# PG06_Schematic_Sheet4.net
KiCad netlist of a schematic drawn in Altium Designer
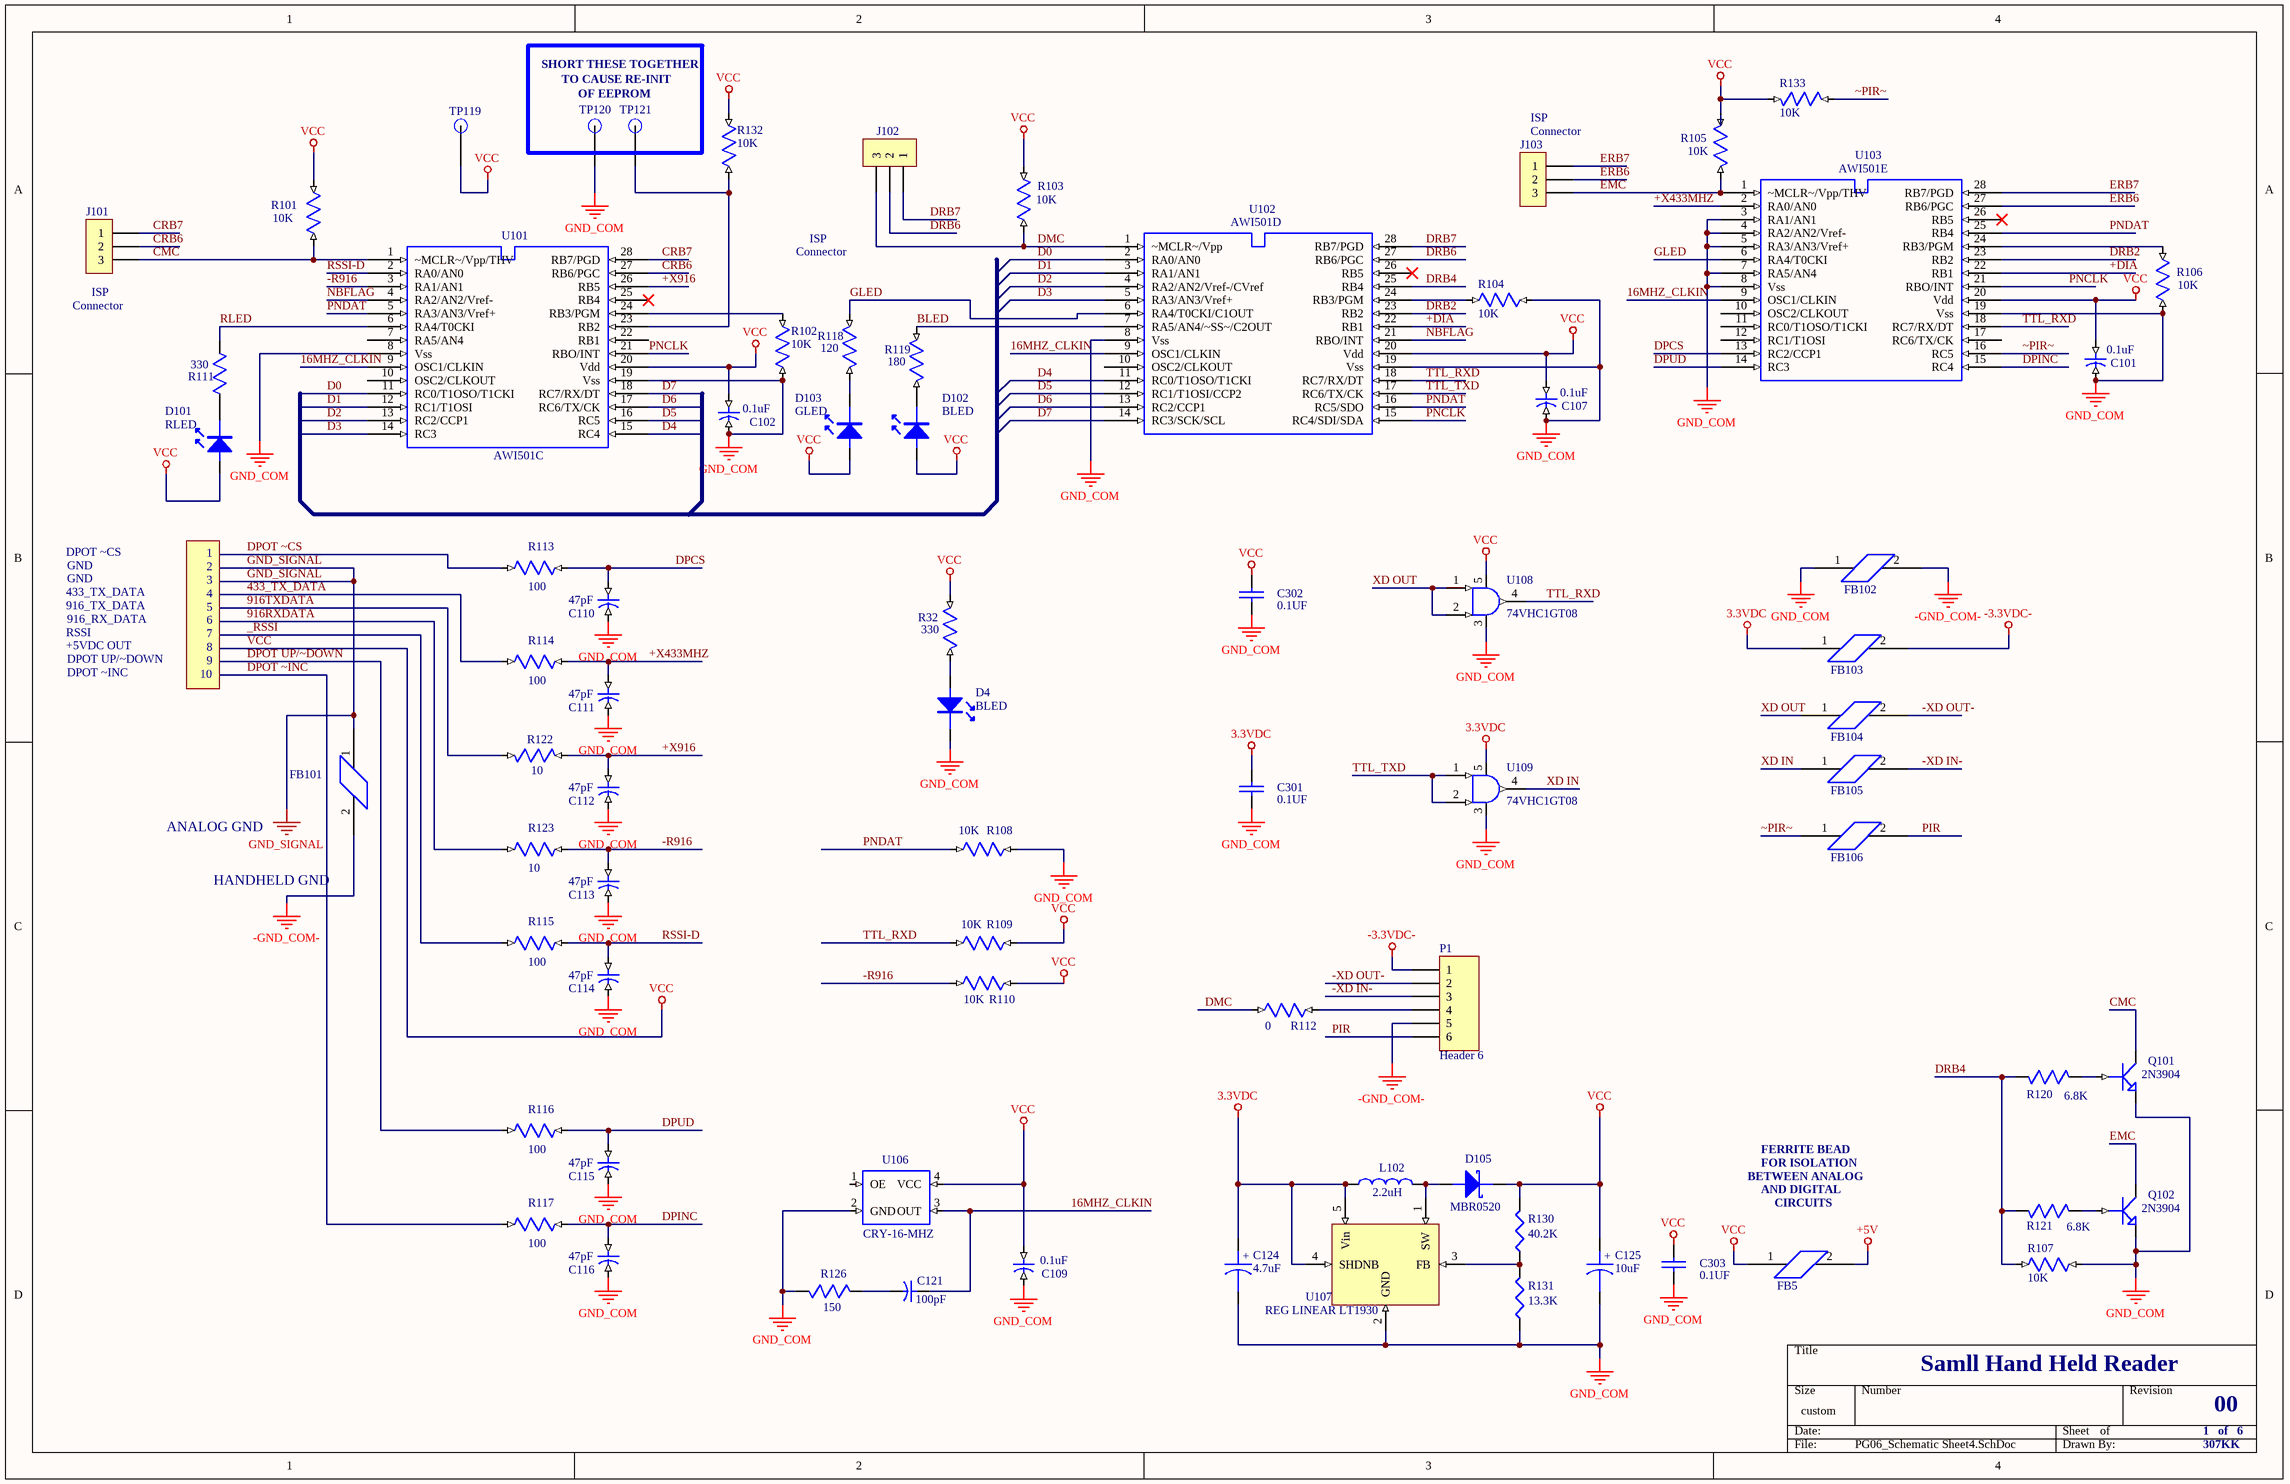
[diagram p0: PG06_Schematic Sheet4.SchDoc]

(export (version "E")
  (design (tool "Eeschema 10.0.6"))
  (components
    (comp (ref "C101") (value "0.1uF") (footprint "0603") (libsource (lib "*") (part "C_603")))
    (comp (ref "C102") (value "0.1uF") (footprint "0603") (libsource (lib "*") (part "C_603")))
    (comp (ref "C107") (value "0.1uF") (footprint "0603") (libsource (lib "*") (part "C_603")))
    (comp (ref "C109") (value "0.1uF") (footprint "0603") (libsource (lib "") (part "C_603_1")))
    (comp (ref "C110") (value "47pF") (footprint "0603") (libsource (lib "*") (part "C0603")))
    (comp (ref "C111") (value "47pF") (footprint "0603") (libsource (lib "*") (part "C0603")))
    (comp (ref "C112") (value "47pF") (footprint "0603") (libsource (lib "*") (part "C0603")))
    (comp (ref "C113") (value "47pF") (footprint "0603") (libsource (lib "*") (part "C0603")))
    (comp (ref "C114") (value "47pF") (footprint "0603") (libsource (lib "*") (part "C0603")))
    (comp (ref "C115") (value "47pF") (footprint "0603") (libsource (lib "*") (part "C0603")))
    (comp (ref "C116") (value "47pF") (footprint "0603") (libsource (lib "*") (part "C0603")))
    (comp (ref "C121") (value "100pF") (footprint "0603") (libsource (lib "*") (part "C_0603")))
    (comp (ref "C124")
      (value "4.7uF")
      (footprint "CAP A CASE")
      (description "Capacitor")
      (libsource (lib "*") (part "CAPACITOR POL"))
    )
    (comp (ref "C125")
      (value "10uF")
      (footprint "CAP A CASE")
      (description "Capacitor")
      (libsource (lib "*") (part "CAPACITOR POL"))
    )
    (comp (ref "C301")
      (value "0.1UF")
      (footprint "0603")
      (description "Capacitor")
      (libsource (lib "*") (part "CAP"))
    )
    (comp (ref "C302")
      (value "0.1UF")
      (footprint "0603")
      (description "Capacitor")
      (libsource (lib "*") (part "CAP"))
    )
    (comp (ref "C303")
      (value "0.1UF")
      (footprint "0603")
      (description "Capacitor")
      (libsource (lib "*") (part "CAP"))
    )
    (comp (ref "D4") (value "BLED") (footprint "404-1032-2-ND") (libsource (lib "*") (part "LED")))
    (comp (ref "D101") (value "RLED") (footprint "404-1032-2-ND") (libsource (lib "*") (part "LED")))
    (comp (ref "D102") (value "BLED") (footprint "404-1032-2-ND") (libsource (lib "*") (part "LED")))
    (comp (ref "D103") (value "GLED") (footprint "404-1032-2-ND") (libsource (lib "*") (part "LED")))
    (comp (ref "D105")
      (value "MBR0520")
      (footprint "SOD123_021405")
      (description "Schottky Diode")
      (libsource (lib "*") (part "DIODE SCHOTTKY"))
    )
    (comp (ref "FB5") (value "FB") (footprint "0603") (libsource (lib "*") (part "FB_0603")))
    (comp (ref "FB101") (value "FB") (footprint "0603") (libsource (lib "*") (part "FB_0603")))
    (comp (ref "FB102") (value "FB") (footprint "0603") (libsource (lib "*") (part "FB_0603")))
    (comp (ref "FB103") (value "FB") (footprint "0603") (libsource (lib "*") (part "FB_0603")))
    (comp (ref "FB104") (value "FB") (footprint "0603") (libsource (lib "*") (part "FB_0603")))
    (comp (ref "FB105") (value "FB") (footprint "0603") (libsource (lib "*") (part "FB_0603")))
    (comp (ref "FB106") (value "FB") (footprint "0603") (libsource (lib "*") (part "FB_0603")))
    (comp (ref "J101")
      (value "1X3 HEADER")
      (footprint "1X3 HEADER TEST PADS")
      (description "Connector")
      (libsource (lib "*") (part "CON3"))
    )
    (comp (ref "J102")
      (value "1X3 HEADER")
      (footprint "1X3 HEADER TEST PADS")
      (description "Connector")
      (libsource (lib "") (part "CON3_1"))
    )
    (comp (ref "J103")
      (value "1X3 HEADER")
      (footprint "1X3 HEADER TEST PADS")
      (description "Connector")
      (libsource (lib "*") (part "CON3"))
    )
    (comp (ref "L102")
      (value "2.2uH")
      (footprint "COIL BOURNS SDR7030-330M")
      (libsource (lib "*") (part "INDUCTOR1"))
    )
    (comp (ref "P1")
      (value "Header 6")
      (footprint "1X6 HEADER")
      (description "Header, 6-Pin")
      (fields (field (name "PUBLISHER") "Altium Limited"))
      (libsource (lib "Miscellaneous Connectors") (part "Header 6"))
    )
    (comp (ref "Q101")
      (value "2N3904")
      (footprint "SOT23 TRANS")
      (description "NPN Transistor")
      (libsource (lib "*") (part "NPN1"))
    )
    (comp (ref "Q102")
      (value "2N3904")
      (footprint "SOT23 TRANS")
      (description "NPN Transistor")
      (libsource (lib "*") (part "NPN1"))
    )
    (comp (ref "R32") (value "330") (footprint "0603") (libsource (lib "*") (part "R0402")))
    (comp (ref "R101") (value "10K") (footprint "0603") (libsource (lib "*") (part "R_603")))
    (comp (ref "R102") (value "10K") (footprint "0603") (libsource (lib "*") (part "R_603")))
    (comp (ref "R103") (value "10K") (footprint "0603") (libsource (lib "*") (part "R_603")))
    (comp (ref "R104") (value "10K") (footprint "0603") (libsource (lib "*") (part "R_603")))
    (comp (ref "R105") (value "10K") (footprint "0603") (libsource (lib "*") (part "R_603")))
    (comp (ref "R106") (value "10K") (footprint "0603") (libsource (lib "*") (part "R_603")))
    (comp (ref "R107") (value "10K") (footprint "0603") (libsource (lib "*") (part "R_603")))
    (comp (ref "R108") (value "10K") (footprint "0603") (libsource (lib "*") (part "R_603")))
    (comp (ref "R109") (value "10K") (footprint "0603") (libsource (lib "*") (part "R_603")))
    (comp (ref "R110") (value "10K") (footprint "0603") (libsource (lib "*") (part "R_603")))
    (comp (ref "R111") (value "330") (footprint "0603") (libsource (lib "*") (part "R_0603")))
    (comp (ref "R112") (value "0") (footprint "0603") (libsource (lib "*") (part "R_603")))
    (comp (ref "R113") (value "100") (footprint "0603") (libsource (lib "*") (part "R0603")))
    (comp (ref "R114") (value "100") (footprint "0603") (libsource (lib "*") (part "R0603")))
    (comp (ref "R115") (value "100") (footprint "0603") (libsource (lib "*") (part "R0603")))
    (comp (ref "R116") (value "100") (footprint "0603") (libsource (lib "*") (part "R0603")))
    (comp (ref "R117") (value "100") (footprint "0603") (libsource (lib "*") (part "R0603")))
    (comp (ref "R118") (value "120") (footprint "0603") (libsource (lib "*") (part "R0402")))
    (comp (ref "R119") (value "180") (footprint "0603") (libsource (lib "*") (part "R0402")))
    (comp (ref "R120") (value "6.8K") (footprint "0603") (libsource (lib "*") (part "R_0603")))
    (comp (ref "R121") (value "6.8K") (footprint "0603") (libsource (lib "*") (part "R_0603")))
    (comp (ref "R122") (value "10") (footprint "0603") (libsource (lib "*") (part "R_603")))
    (comp (ref "R123") (value "10") (footprint "0603") (libsource (lib "*") (part "R0603")))
    (comp (ref "R126") (value "150") (footprint "0603") (libsource (lib "*") (part "R_0603")))
    (comp (ref "R130") (value "40.2K") (footprint "0603") (libsource (lib "*") (part "RES1")))
    (comp (ref "R131") (value "13.3K") (footprint "0603") (libsource (lib "*") (part "RES1")))
    (comp (ref "R132") (value "10K") (footprint "0603") (libsource (lib "*") (part "R_603")))
    (comp (ref "R133") (value "10K") (footprint "0603") (libsource (lib "*") (part "R_603")))
    (comp (ref "TP119") (value "TP") (footprint "TESTPOINT_SMT") (libsource (lib "*") (part "TESTPOINT_1")))
    (comp (ref "TP120") (value "TP") (footprint "TESTPOINT_SMT") (libsource (lib "*") (part "TESTPOINT_1")))
    (comp (ref "TP121") (value "TP") (footprint "TESTPOINT") (libsource (lib "*") (part "TESTPOINT_1")))
    (comp (ref "U101") (value "AWI501C") (footprint "SSOP28") (libsource (lib "*") (part "PIC16F870")))
    (comp (ref "U102") (value "AWI501D") (footprint "SSOP28") (libsource (lib "*") (part "PIC16F876A")))
    (comp (ref "U103") (value "AWI501E") (footprint "SSOP28") (libsource (lib "*") (part "PIC16F870")))
    (comp (ref "U106")
      (value "CRY-16-MHZ")
      (footprint "SMT OSCILLATOR")
      (libsource (lib "*") (part "CRY-SMD-5-7"))
    )
    (comp (ref "U107")
      (value "REG LINEAR LT1930")
      (footprint "SOT23-5A")
      (libsource (lib "*") (part "REG LINEAR LT1930"))
    )
    (comp (ref "U108")
      (value "74VHC1GT08")
      (footprint "SC70")
      (description "Single AND Gate")
      (fields (field (name "PART NO") "NEW") (field (name "Comment") "Single And Gate"))
      (libsource (lib "Common") (part "7408_SINGLE"))
    )
    (comp (ref "U109")
      (value "74VHC1GT08")
      (footprint "SC70")
      (description "Single AND Gate")
      (fields (field (name "PART NO") "NC7SZ08P5X"))
      (libsource (lib "Common") (part "7408_SINGLE"))
    )
  )
  (nets
    (net (code "1") (name "+5V") (class "Default")
      (node (ref "FB5") (pin "2") (pinfunction "1_2") (pintype "passive"))
    )
    (net (code "2") (name "-3.3VDC-") (class "Default")
      (node (ref "FB103") (pin "2") (pinfunction "1_2") (pintype "passive"))
      (node (ref "P1") (pin "1") (pinfunction "1_1") (pintype "passive"))
    )
    (net (code "3") (name "-GND_COM-") (class "Default")
      (node (ref "FB101") (pin "2") (pinfunction "1_2") (pintype "passive"))
      (node (ref "FB102") (pin "2") (pinfunction "1_2") (pintype "passive"))
      (node (ref "P1") (pin "5") (pinfunction "5_5") (pintype "passive"))
    )
    (net (code "4") (name "/+DIA") (class "Default")
      (node (ref "U102") (pin "22") (pinfunction "RB1_22") (pintype "input"))
      (node (ref "U103") (pin "22") (pinfunction "RB1_22") (pintype "input"))
    )
    (net (code "5") (name "/+X433MHZ") (class "Default")
      (node (ref "C111") (pin "1") (pinfunction "A_1") (pintype "input"))
      (node (ref "R114") (pin "2") (pinfunction "B_2") (pintype "input"))
      (node (ref "U103") (pin "2") (pinfunction "RA0/AN0_2") (pintype "input"))
    )
    (net (code "6") (name "/+X916") (class "Default")
      (node (ref "C112") (pin "1") (pinfunction "A_1") (pintype "input"))
      (node (ref "R122") (pin "1") (pinfunction "A_1") (pintype "input"))
      (node (ref "U101") (pin "26") (pinfunction "RB5_26") (pintype "input"))
    )
    (net (code "7") (name "/-R916") (class "Default")
      (node (ref "C113") (pin "1") (pinfunction "A_1") (pintype "input"))
      (node (ref "R110") (pin "2") (pinfunction "B_2") (pintype "input"))
      (node (ref "R123") (pin "2") (pinfunction "B_2") (pintype "input"))
      (node (ref "U101") (pin "3") (pinfunction "RA1/AN1_3") (pintype "input"))
    )
    (net (code "8") (name "/-XD IN-") (class "Default")
      (node (ref "FB105") (pin "2") (pinfunction "1_2") (pintype "passive"))
      (node (ref "P1") (pin "3") (pinfunction "3_3") (pintype "passive"))
    )
    (net (code "9") (name "/-XD OUT-") (class "Default")
      (node (ref "FB104") (pin "2") (pinfunction "1_2") (pintype "passive"))
      (node (ref "P1") (pin "2") (pinfunction "2_2") (pintype "passive"))
    )
    (net (code "10") (name "/16MHZ_CLKIN") (class "Default")
      (node (ref "C121") (pin "1") (pinfunction "A_1") (pintype "passive"))
      (node (ref "U101") (pin "9") (pinfunction "OSC1/CLKIN_9") (pintype "input"))
      (node (ref "U102") (pin "9") (pinfunction "OSC1/CLKIN_9") (pintype "input"))
      (node (ref "U103") (pin "9") (pinfunction "OSC1/CLKIN_9") (pintype "input"))
      (node (ref "U106") (pin "3") (pinfunction "OUT_3") (pintype "input"))
    )
    (net (code "11") (name "/433_TX_DATA") (class "Default")
      (node (ref "R114") (pin "1") (pinfunction "A_1") (pintype "input"))
    )
    (net (code "12") (name "/916RXDATA") (class "Default")
      (node (ref "R123") (pin "1") (pinfunction "A_1") (pintype "input"))
    )
    (net (code "13") (name "/916TXDATA") (class "Default")
      (node (ref "R122") (pin "2") (pinfunction "B_2") (pintype "input"))
    )
    (net (code "14") (name "/BLED") (class "Default")
      (node (ref "R119") (pin "2") (pinfunction "B_2") (pintype "input"))
      (node (ref "U102") (pin "7") (pinfunction "RA5/AN4/~SS~/C2OUT_7") (pintype "input"))
    )
    (net (code "15") (name "/CMC") (class "Default")
      (node (ref "J101") (pin "3") (pinfunction "3_3") (pintype "passive"))
      (node (ref "Q101") (pin "C") (pinfunction "C_C") (pintype "passive"))
      (node (ref "R101") (pin "2") (pinfunction "B_2") (pintype "input"))
      (node (ref "U101") (pin "1") (pinfunction "~MCLR~/Vpp/THV_1") (pintype "input"))
    )
    (net (code "16") (name "/CRB6") (class "Default")
      (node (ref "J101") (pin "2") (pinfunction "2_2") (pintype "passive"))
      (node (ref "U101") (pin "27") (pinfunction "RB6/PGC_27") (pintype "input"))
    )
    (net (code "17") (name "/CRB7") (class "Default")
      (node (ref "J101") (pin "1") (pinfunction "1_1") (pintype "passive"))
      (node (ref "U101") (pin "28") (pinfunction "RB7/PGD_28") (pintype "input"))
    )
    (net (code "18") (name "/D0") (class "Default")
      (node (ref "U101") (pin "11") (pinfunction "RC0/T1OSO/T1CKI_11") (pintype "input"))
      (node (ref "U102") (pin "2") (pinfunction "RA0/AN0_2") (pintype "input"))
    )
    (net (code "19") (name "/D1") (class "Default")
      (node (ref "U101") (pin "12") (pinfunction "RC1/T1OSI_12") (pintype "input"))
      (node (ref "U102") (pin "3") (pinfunction "RA1/AN1_3") (pintype "input"))
    )
    (net (code "20") (name "/D2") (class "Default")
      (node (ref "U101") (pin "13") (pinfunction "RC2/CCP1_13") (pintype "input"))
      (node (ref "U102") (pin "4") (pinfunction "RA2/AN2/Vref-/CVref_4") (pintype "input"))
    )
    (net (code "21") (name "/D3") (class "Default")
      (node (ref "U101") (pin "14") (pinfunction "RC3_14") (pintype "input"))
      (node (ref "U102") (pin "5") (pinfunction "RA3/AN3/Vref+_5") (pintype "input"))
    )
    (net (code "22") (name "/D4") (class "Default")
      (node (ref "U101") (pin "15") (pinfunction "RC4_15") (pintype "input"))
      (node (ref "U102") (pin "11") (pinfunction "RC0/T1OSO/T1CKI_11") (pintype "input"))
    )
    (net (code "23") (name "/D5") (class "Default")
      (node (ref "U101") (pin "16") (pinfunction "RC5_16") (pintype "input"))
      (node (ref "U102") (pin "12") (pinfunction "RC1/T1OSI/CCP2_12") (pintype "input"))
    )
    (net (code "24") (name "/D6") (class "Default")
      (node (ref "U101") (pin "17") (pinfunction "RC6/TX/CK_17") (pintype "input"))
      (node (ref "U102") (pin "13") (pinfunction "RC2/CCP1_13") (pintype "input"))
    )
    (net (code "25") (name "/D7") (class "Default")
      (node (ref "U101") (pin "18") (pinfunction "RC7/RX/DT_18") (pintype "input"))
      (node (ref "U102") (pin "14") (pinfunction "RC3/SCK/SCL_14") (pintype "input"))
    )
    (net (code "26") (name "/DMC") (class "Default")
      (node (ref "J102") (pin "3") (pinfunction "3_3") (pintype "passive"))
      (node (ref "R103") (pin "2") (pinfunction "B_2") (pintype "input"))
      (node (ref "R112") (pin "2") (pinfunction "B_2") (pintype "input"))
      (node (ref "U102") (pin "1") (pinfunction "~MCLR~/Vpp_1") (pintype "input"))
    )
    (net (code "27") (name "/DPCS") (class "Default")
      (node (ref "C110") (pin "1") (pinfunction "A_1") (pintype "input"))
      (node (ref "R113") (pin "2") (pinfunction "B_2") (pintype "input"))
      (node (ref "U103") (pin "13") (pinfunction "RC2/CCP1_13") (pintype "input"))
    )
    (net (code "28") (name "/DPINC") (class "Default")
      (node (ref "C116") (pin "1") (pinfunction "A_1") (pintype "input"))
      (node (ref "R117") (pin "2") (pinfunction "B_2") (pintype "input"))
      (node (ref "U103") (pin "15") (pinfunction "RC4_15") (pintype "input"))
    )
    (net (code "29") (name "/DPOT UP{slash}~DOWN") (class "Default")
      (node (ref "R116") (pin "1") (pinfunction "A_1") (pintype "input"))
    )
    (net (code "30") (name "/DPOT ~CS") (class "Default")
      (node (ref "R113") (pin "1") (pinfunction "A_1") (pintype "input"))
    )
    (net (code "31") (name "/DPOT ~INC") (class "Default")
      (node (ref "R117") (pin "1") (pinfunction "A_1") (pintype "input"))
    )
    (net (code "32") (name "/DPUD") (class "Default")
      (node (ref "C115") (pin "1") (pinfunction "A_1") (pintype "input"))
      (node (ref "R116") (pin "2") (pinfunction "B_2") (pintype "input"))
      (node (ref "U103") (pin "14") (pinfunction "RC3_14") (pintype "input"))
    )
    (net (code "33") (name "/DRB2") (class "Default")
      (node (ref "U102") (pin "23") (pinfunction "RB2_23") (pintype "input"))
      (node (ref "U103") (pin "23") (pinfunction "RB2_23") (pintype "input"))
    )
    (net (code "34") (name "/DRB4") (class "Default")
      (node (ref "R107") (pin "1") (pinfunction "A_1") (pintype "input"))
      (node (ref "R120") (pin "1") (pinfunction "A_1") (pintype "passive"))
      (node (ref "R121") (pin "1") (pinfunction "A_1") (pintype "passive"))
      (node (ref "U102") (pin "25") (pinfunction "RB4_25") (pintype "input"))
    )
    (net (code "35") (name "/DRB6") (class "Default")
      (node (ref "J102") (pin "2") (pinfunction "2_2") (pintype "passive"))
      (node (ref "U102") (pin "27") (pinfunction "RB6/PGC_27") (pintype "input"))
    )
    (net (code "36") (name "/DRB7") (class "Default")
      (node (ref "J102") (pin "1") (pinfunction "1_1") (pintype "passive"))
      (node (ref "U102") (pin "28") (pinfunction "RB7/PGD_28") (pintype "input"))
    )
    (net (code "37") (name "/EMC") (class "Default")
      (node (ref "J103") (pin "3") (pinfunction "3_3") (pintype "passive"))
      (node (ref "Q102") (pin "C") (pinfunction "C_C") (pintype "passive"))
      (node (ref "R105") (pin "2") (pinfunction "B_2") (pintype "input"))
      (node (ref "U103") (pin "1") (pinfunction "~MCLR~/Vpp/THV_1") (pintype "input"))
    )
    (net (code "38") (name "/ERB6") (class "Default")
      (node (ref "J103") (pin "2") (pinfunction "2_2") (pintype "passive"))
      (node (ref "U103") (pin "27") (pinfunction "RB6/PGC_27") (pintype "input"))
    )
    (net (code "39") (name "/ERB7") (class "Default")
      (node (ref "J103") (pin "1") (pinfunction "1_1") (pintype "passive"))
      (node (ref "U103") (pin "28") (pinfunction "RB7/PGD_28") (pintype "input"))
    )
    (net (code "40") (name "/GLED") (class "Default")
      (node (ref "R118") (pin "2") (pinfunction "B_2") (pintype "input"))
      (node (ref "U102") (pin "6") (pinfunction "RA4/T0CKI/C1OUT_6") (pintype "input"))
      (node (ref "U103") (pin "6") (pinfunction "RA4/T0CKI_6") (pintype "input"))
    )
    (net (code "41") (name "/NBFLAG") (class "Default")
      (node (ref "U101") (pin "4") (pinfunction "RA2/AN2/Vref-_4") (pintype "input"))
      (node (ref "U102") (pin "21") (pinfunction "RBO/INT_21") (pintype "input"))
    )
    (net (code "42") (name "/PIR") (class "Default")
      (node (ref "FB106") (pin "2") (pinfunction "1_2") (pintype "passive"))
      (node (ref "P1") (pin "6") (pinfunction "6_6") (pintype "passive"))
    )
    (net (code "43") (name "/PNCLK") (class "Default")
      (node (ref "U101") (pin "21") (pinfunction "RBO/INT_21") (pintype "input"))
      (node (ref "U102") (pin "15") (pinfunction "RC4/SDI/SDA_15") (pintype "input"))
      (node (ref "U103") (pin "21") (pinfunction "RBO/INT_21") (pintype "input"))
    )
    (net (code "44") (name "/PNDAT") (class "Default")
      (node (ref "R108") (pin "2") (pinfunction "B_2") (pintype "input"))
      (node (ref "U101") (pin "5") (pinfunction "RA3/AN3/Vref+_5") (pintype "input"))
      (node (ref "U102") (pin "16") (pinfunction "RC5/SDO_16") (pintype "input"))
      (node (ref "U103") (pin "25") (pinfunction "RB4_25") (pintype "input"))
    )
    (net (code "45") (name "/RLED") (class "Default")
      (node (ref "R111") (pin "2") (pinfunction "B_2") (pintype "passive"))
      (node (ref "U101") (pin "6") (pinfunction "RA4/T0CKI_6") (pintype "input"))
    )
    (net (code "46") (name "/RSSI-D") (class "Default")
      (node (ref "C114") (pin "1") (pinfunction "A_1") (pintype "input"))
      (node (ref "R115") (pin "2") (pinfunction "B_2") (pintype "input"))
      (node (ref "U101") (pin "2") (pinfunction "RA0/AN0_2") (pintype "input"))
    )
    (net (code "47") (name "/TTL_RXD") (class "Default")
      (node (ref "R109") (pin "2") (pinfunction "B_2") (pintype "input"))
      (node (ref "U102") (pin "18") (pinfunction "RC7/RX/DT_18") (pintype "input"))
      (node (ref "U103") (pin "18") (pinfunction "RC7/RX/DT_18") (pintype "input"))
      (node (ref "U108") (pin "4") (pinfunction "OUTY_4") (pintype "output"))
    )
    (net (code "48") (name "/TTL_TXD") (class "Default")
      (node (ref "U102") (pin "17") (pinfunction "RC6/TX/CK_17") (pintype "input"))
      (node (ref "U109") (pin "1") (pinfunction "INB_1") (pintype "input"))
      (node (ref "U109") (pin "2") (pinfunction "INA_2") (pintype "input"))
    )
    (net (code "49") (name "/XD IN") (class "Default")
      (node (ref "FB105") (pin "1") (pinfunction "2_1") (pintype "passive"))
      (node (ref "U109") (pin "4") (pinfunction "OUTY_4") (pintype "output"))
    )
    (net (code "50") (name "/XD OUT") (class "Default")
      (node (ref "FB104") (pin "1") (pinfunction "2_1") (pintype "passive"))
      (node (ref "U108") (pin "1") (pinfunction "INB_1") (pintype "input"))
      (node (ref "U108") (pin "2") (pinfunction "INA_2") (pintype "input"))
    )
    (net (code "51") (name "/_RSSI") (class "Default")
      (node (ref "R115") (pin "1") (pinfunction "A_1") (pintype "input"))
    )
    (net (code "52") (name "/~PIR~") (class "Default")
      (node (ref "FB106") (pin "1") (pinfunction "2_1") (pintype "passive"))
      (node (ref "R133") (pin "2") (pinfunction "B_2") (pintype "input"))
      (node (ref "U103") (pin "16") (pinfunction "RC5_16") (pintype "input"))
    )
    (net (code "53") (name "3.3VDC") (class "Default")
      (node (ref "C124") (pin "1") (pinfunction "1_1") (pintype "passive"))
      (node (ref "C301") (pin "1") (pinfunction "1_1") (pintype "passive"))
      (node (ref "FB103") (pin "1") (pinfunction "2_1") (pintype "passive"))
      (node (ref "L102") (pin "1") (pinfunction "1_1") (pintype "passive"))
      (node (ref "U107") (pin "4") (pinfunction "SHDNB_4") (pintype "input"))
      (node (ref "U107") (pin "5") (pinfunction "Vin_5") (pintype "input"))
      (node (ref "U109") (pin "5") (pinfunction "VCC_5") (pintype "power_in"))
    )
    (net (code "54") (name "GND_COM") (class "Default")
      (node (ref "C101") (pin "2") (pinfunction "B_2") (pintype "input"))
      (node (ref "C102") (pin "2") (pinfunction "B_2") (pintype "input"))
      (node (ref "C107") (pin "2") (pinfunction "B_2") (pintype "input"))
      (node (ref "C109") (pin "2") (pinfunction "B_2") (pintype "input"))
      (node (ref "C110") (pin "2") (pinfunction "B_2") (pintype "input"))
      (node (ref "C111") (pin "2") (pinfunction "B_2") (pintype "input"))
      (node (ref "C112") (pin "2") (pinfunction "B_2") (pintype "input"))
      (node (ref "C113") (pin "2") (pinfunction "B_2") (pintype "input"))
      (node (ref "C114") (pin "2") (pinfunction "B_2") (pintype "input"))
      (node (ref "C115") (pin "2") (pinfunction "B_2") (pintype "input"))
      (node (ref "C116") (pin "2") (pinfunction "B_2") (pintype "input"))
      (node (ref "C124") (pin "2") (pinfunction "2_2") (pintype "passive"))
      (node (ref "C125") (pin "2") (pinfunction "2_2") (pintype "passive"))
      (node (ref "C301") (pin "2") (pinfunction "2_2") (pintype "passive"))
      (node (ref "C302") (pin "2") (pinfunction "2_2") (pintype "passive"))
      (node (ref "C303") (pin "2") (pinfunction "2_2") (pintype "passive"))
      (node (ref "D4") (pin "K") (pinfunction "K_K") (pintype "passive"))
      (node (ref "FB102") (pin "1") (pinfunction "2_1") (pintype "passive"))
      (node (ref "Q101") (pin "E") (pinfunction "E_E") (pintype "passive"))
      (node (ref "Q102") (pin "E") (pinfunction "E_E") (pintype "passive"))
      (node (ref "R102") (pin "2") (pinfunction "B_2") (pintype "input"))
      (node (ref "R104") (pin "1") (pinfunction "A_1") (pintype "input"))
      (node (ref "R106") (pin "2") (pinfunction "B_2") (pintype "input"))
      (node (ref "R107") (pin "2") (pinfunction "B_2") (pintype "input"))
      (node (ref "R108") (pin "1") (pinfunction "A_1") (pintype "input"))
      (node (ref "R126") (pin "2") (pinfunction "B_2") (pintype "passive"))
      (node (ref "R131") (pin "1") (pinfunction "1_1") (pintype "passive"))
      (node (ref "TP120") (pin "1") (pinfunction "TP_1") (pintype "passive"))
      (node (ref "U101") (pin "19") (pinfunction "Vss_19") (pintype "input"))
      (node (ref "U101") (pin "8") (pinfunction "Vss_8") (pintype "input"))
      (node (ref "U102") (pin "19") (pinfunction "Vss_19") (pintype "input"))
      (node (ref "U102") (pin "8") (pinfunction "Vss_8") (pintype "input"))
      (node (ref "U103") (pin "19") (pinfunction "Vss_19") (pintype "input"))
      (node (ref "U103") (pin "3") (pinfunction "RA1/AN1_3") (pintype "input"))
      (node (ref "U103") (pin "4") (pinfunction "RA2/AN2/Vref-_4") (pintype "input"))
      (node (ref "U103") (pin "5") (pinfunction "RA3/AN3/Vref+_5") (pintype "input"))
      (node (ref "U103") (pin "7") (pinfunction "RA5/AN4_7") (pintype "input"))
      (node (ref "U103") (pin "8") (pinfunction "Vss_8") (pintype "input"))
      (node (ref "U106") (pin "2") (pinfunction "GND_2") (pintype "input"))
      (node (ref "U107") (pin "2") (pinfunction "GND_2") (pintype "input"))
      (node (ref "U108") (pin "3") (pinfunction "GND_3") (pintype "power_in"))
      (node (ref "U109") (pin "3") (pinfunction "GND_3") (pintype "power_in"))
    )
    (net (code "55") (name "GND_SIGNAL") (class "Default")
      (node (ref "FB101") (pin "1") (pinfunction "2_1") (pintype "passive"))
    )
    (net (code "56") (name "Net-(C121-B)") (class "Default")
      (node (ref "C121") (pin "2") (pinfunction "B_2") (pintype "passive"))
      (node (ref "R126") (pin "1") (pinfunction "A_1") (pintype "passive"))
    )
    (net (code "57") (name "Net-(R32-A)") (class "Default")
      (node (ref "D4") (pin "A") (pinfunction "A_A") (pintype "passive"))
      (node (ref "R32") (pin "1") (pinfunction "A_1") (pintype "input"))
    )
    (net (code "58") (name "Net-(R102-A)") (class "Default")
      (node (ref "R102") (pin "1") (pinfunction "A_1") (pintype "input"))
      (node (ref "U101") (pin "24") (pinfunction "RB3/PGM_24") (pintype "input"))
    )
    (net (code "59") (name "Net-(R104-B)") (class "Default")
      (node (ref "R104") (pin "2") (pinfunction "B_2") (pintype "input"))
      (node (ref "U102") (pin "24") (pinfunction "RB3/PGM_24") (pintype "input"))
    )
    (net (code "60") (name "Net-(R106-A)") (class "Default")
      (node (ref "R106") (pin "1") (pinfunction "A_1") (pintype "input"))
      (node (ref "U103") (pin "24") (pinfunction "RB3/PGM_24") (pintype "input"))
    )
    (net (code "61") (name "Net-(R111-A)") (class "Default")
      (node (ref "D101") (pin "K") (pinfunction "K_K") (pintype "passive"))
      (node (ref "R111") (pin "1") (pinfunction "A_1") (pintype "passive"))
    )
    (net (code "62") (name "Net-(R112-A)") (class "Default")
      (node (ref "P1") (pin "4") (pinfunction "4_4") (pintype "passive"))
      (node (ref "R112") (pin "1") (pinfunction "A_1") (pintype "input"))
    )
    (net (code "63") (name "Net-(R118-A)") (class "Default")
      (node (ref "D103") (pin "K") (pinfunction "K_K") (pintype "passive"))
      (node (ref "R118") (pin "1") (pinfunction "A_1") (pintype "input"))
    )
    (net (code "64") (name "Net-(R119-A)") (class "Default")
      (node (ref "D102") (pin "K") (pinfunction "K_K") (pintype "passive"))
      (node (ref "R119") (pin "1") (pinfunction "A_1") (pintype "input"))
    )
    (net (code "65") (name "Net-(R120-B)") (class "Default")
      (node (ref "Q101") (pin "B") (pinfunction "B_B") (pintype "input"))
      (node (ref "R120") (pin "2") (pinfunction "B_2") (pintype "passive"))
    )
    (net (code "66") (name "Net-(R121-B)") (class "Default")
      (node (ref "Q102") (pin "B") (pinfunction "B_B") (pintype "input"))
      (node (ref "R121") (pin "2") (pinfunction "B_2") (pintype "passive"))
    )
    (net (code "67") (name "Net-(R132-B)") (class "Default")
      (node (ref "R132") (pin "2") (pinfunction "B_2") (pintype "input"))
      (node (ref "TP121") (pin "1") (pinfunction "TP_1") (pintype "passive"))
      (node (ref "U101") (pin "23") (pinfunction "RB2_23") (pintype "input"))
    )
    (net (code "68") (name "Net-(U107-FB)") (class "Default")
      (node (ref "R130") (pin "1") (pinfunction "1_1") (pintype "passive"))
      (node (ref "R131") (pin "2") (pinfunction "2_2") (pintype "passive"))
      (node (ref "U107") (pin "3") (pinfunction "FB_3") (pintype "input"))
    )
    (net (code "69") (name "Net-(U107-SW)") (class "Default")
      (node (ref "D105") (pin "A") (pinfunction "A_A") (pintype "passive"))
      (node (ref "L102") (pin "2") (pinfunction "2_2") (pintype "passive"))
      (node (ref "U107") (pin "1") (pinfunction "SW_1") (pintype "input"))
    )
    (net (code "70") (name "VCC") (class "Default")
      (node (ref "C101") (pin "1") (pinfunction "A_1") (pintype "input"))
      (node (ref "C102") (pin "1") (pinfunction "A_1") (pintype "input"))
      (node (ref "C107") (pin "1") (pinfunction "A_1") (pintype "input"))
      (node (ref "C109") (pin "1") (pinfunction "A_1") (pintype "input"))
      (node (ref "C125") (pin "1") (pinfunction "1_1") (pintype "passive"))
      (node (ref "C302") (pin "1") (pinfunction "1_1") (pintype "passive"))
      (node (ref "C303") (pin "1") (pinfunction "1_1") (pintype "passive"))
      (node (ref "D101") (pin "A") (pinfunction "A_A") (pintype "passive"))
      (node (ref "D102") (pin "A") (pinfunction "A_A") (pintype "passive"))
      (node (ref "D103") (pin "A") (pinfunction "A_A") (pintype "passive"))
      (node (ref "D105") (pin "K") (pinfunction "K_K") (pintype "passive"))
      (node (ref "FB5") (pin "1") (pinfunction "2_1") (pintype "passive"))
      (node (ref "R101") (pin "1") (pinfunction "A_1") (pintype "input"))
      (node (ref "R103") (pin "1") (pinfunction "A_1") (pintype "input"))
      (node (ref "R105") (pin "1") (pinfunction "A_1") (pintype "input"))
      (node (ref "R109") (pin "1") (pinfunction "A_1") (pintype "input"))
      (node (ref "R110") (pin "1") (pinfunction "A_1") (pintype "input"))
      (node (ref "R130") (pin "2") (pinfunction "2_2") (pintype "passive"))
      (node (ref "R132") (pin "1") (pinfunction "A_1") (pintype "input"))
      (node (ref "R133") (pin "1") (pinfunction "A_1") (pintype "input"))
      (node (ref "R32") (pin "2") (pinfunction "B_2") (pintype "input"))
      (node (ref "TP119") (pin "1") (pinfunction "TP_1") (pintype "passive"))
      (node (ref "U101") (pin "20") (pinfunction "Vdd_20") (pintype "input"))
      (node (ref "U102") (pin "20") (pinfunction "Vdd_20") (pintype "input"))
      (node (ref "U103") (pin "20") (pinfunction "Vdd_20") (pintype "input"))
      (node (ref "U106") (pin "4") (pinfunction "VCC_4") (pintype "input"))
      (node (ref "U108") (pin "5") (pinfunction "VCC_5") (pintype "power_in"))
    )
    (net (code "71") (name "unconnected-(U101-OSC2{slash}CLKOUT-Pad10)") (class "Default")
      (node (ref "U101") (pin "10") (pinfunction "OSC2/CLKOUT_10") (pintype "input"))
    )
    (net (code "72") (name "unconnected-(U101-RA5{slash}AN4-Pad7)") (class "Default")
      (node (ref "U101") (pin "7") (pinfunction "RA5/AN4_7") (pintype "input"))
    )
    (net (code "73") (name "unconnected-(U101-RB1-Pad22)") (class "Default")
      (node (ref "U101") (pin "22") (pinfunction "RB1_22") (pintype "input"))
    )
    (net (code "74") (name "unconnected-(U101-RB4-Pad25)") (class "Default")
      (node (ref "U101") (pin "25") (pinfunction "RB4_25") (pintype "input+no_connect"))
    )
    (net (code "75") (name "unconnected-(U102-OSC2{slash}CLKOUT-Pad10)") (class "Default")
      (node (ref "U102") (pin "10") (pinfunction "OSC2/CLKOUT_10") (pintype "input"))
    )
    (net (code "76") (name "unconnected-(U102-RB5-Pad26)") (class "Default")
      (node (ref "U102") (pin "26") (pinfunction "RB5_26") (pintype "input+no_connect"))
    )
    (net (code "77") (name "unconnected-(U103-OSC2{slash}CLKOUT-Pad10)") (class "Default")
      (node (ref "U103") (pin "10") (pinfunction "OSC2/CLKOUT_10") (pintype "input"))
    )
    (net (code "78") (name "unconnected-(U103-RB5-Pad26)") (class "Default")
      (node (ref "U103") (pin "26") (pinfunction "RB5_26") (pintype "input+no_connect"))
    )
    (net (code "79") (name "unconnected-(U103-RC0{slash}T1OSO{slash}T1CKI-Pad11)") (class "Default")
      (node (ref "U103") (pin "11") (pinfunction "RC0/T1OSO/T1CKI_11") (pintype "input"))
    )
    (net (code "80") (name "unconnected-(U103-RC1{slash}T1OSI-Pad12)") (class "Default")
      (node (ref "U103") (pin "12") (pinfunction "RC1/T1OSI_12") (pintype "input"))
    )
    (net (code "81") (name "unconnected-(U103-RC6{slash}TX{slash}CK-Pad17)") (class "Default")
      (node (ref "U103") (pin "17") (pinfunction "RC6/TX/CK_17") (pintype "input"))
    )
    (net (code "82") (name "unconnected-(U106-OE-Pad1)") (class "Default")
      (node (ref "U106") (pin "1") (pinfunction "OE_1") (pintype "input"))
    )
  )
)
